# 2014_carte_alim.net
KiCad netlist of a schematic drawn in Altium Designer
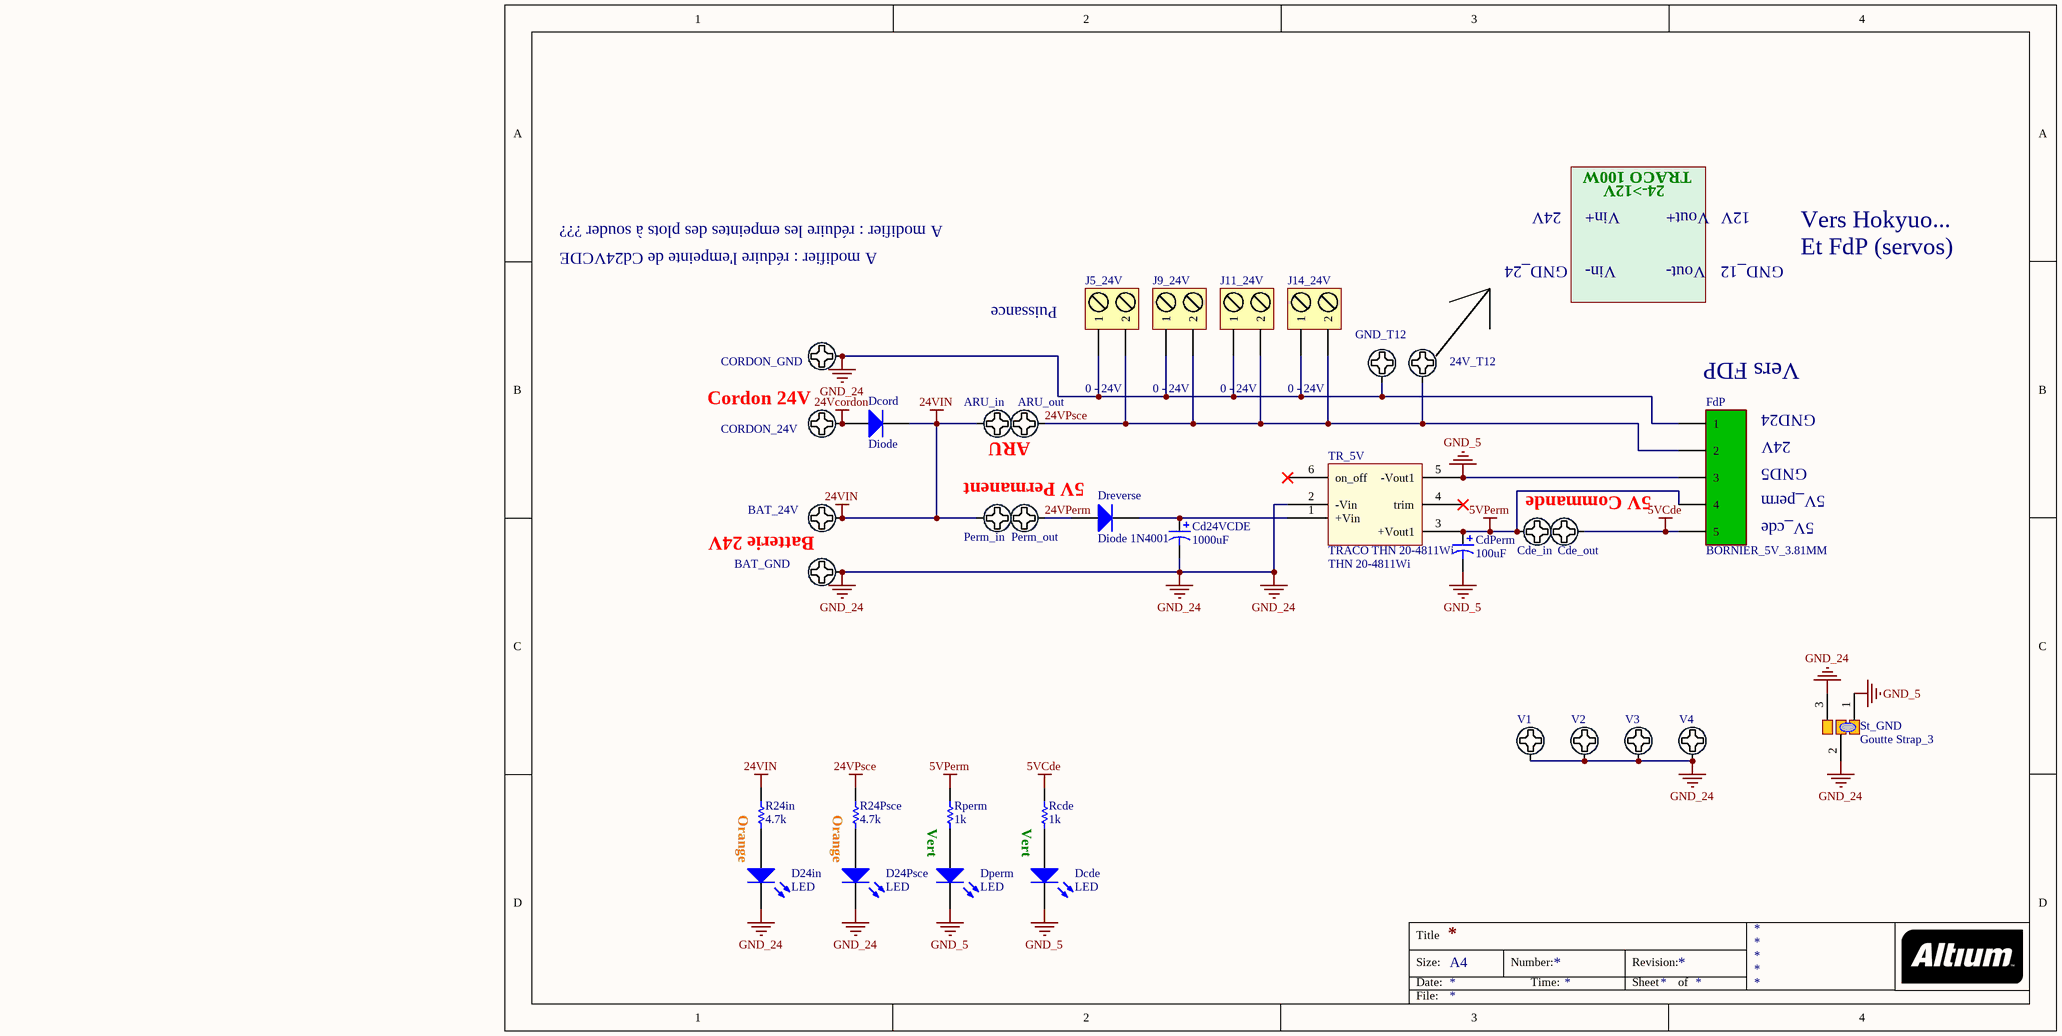
[diagram p0: 2014_carte_alim.SchDoc]

(export (version "E")
  (design (tool "Eeschema 10.0.6"))
  (components
    (comp (ref "24V_T12")
      (value "Pad_M3")
      (footprint "M3x6mm")
      (description "Vis M3 X 6mm _TORX_Tête 6mm")
      (fields (field (name "PUBLISHER") "Damien Guitton"))
      (libsource (lib "_ROBOT") (part "Vis M3 X 6mm _TORX_Tête 6mm"))
    )
    (comp (ref "ARU_in")
      (value "Pad_M3")
      (footprint "M3x6mm")
      (description "Vis M3 X 6mm _TORX_Tête 6mm")
      (fields (field (name "PUBLISHER") "Damien Guitton"))
      (libsource (lib "_ROBOT") (part "Vis M3 X 6mm _TORX_Tête 6mm"))
    )
    (comp (ref "ARU_out")
      (value "Pad_M3")
      (footprint "M3x6mm")
      (description "Vis M3 X 6mm _TORX_Tête 6mm")
      (fields (field (name "PUBLISHER") "Damien Guitton"))
      (libsource (lib "_ROBOT") (part "Vis M3 X 6mm _TORX_Tête 6mm"))
    )
    (comp (ref "BAT_24V")
      (value "Pad_M3")
      (footprint "M3x6mm")
      (description "Vis M3 X 6mm _TORX_Tête 6mm")
      (fields (field (name "PUBLISHER") "Damien Guitton"))
      (libsource (lib "_ROBOT") (part "Vis M3 X 6mm _TORX_Tête 6mm"))
    )
    (comp (ref "BAT_GND")
      (value "Pad_M3")
      (footprint "M3x6mm")
      (description "Vis M3 X 6mm _TORX_Tête 6mm")
      (fields (field (name "PUBLISHER") "Damien Guitton"))
      (libsource (lib "_ROBOT") (part "Vis M3 X 6mm _TORX_Tête 6mm"))
    )
    (comp (ref "Cd24VCDE")
      (value "1000uF")
      (footprint "RESISTANCE_5W")
      (description "Polarized Capacitor")
      (libsource (lib "_ROBOT") (part "Condensateur Polarise Traversant"))
    )
    (comp (ref "Cde_in")
      (value "Pad_M3")
      (footprint "M3x6mm")
      (description "Vis M3 X 6mm _TORX_Tête 6mm")
      (fields (field (name "PUBLISHER") "Damien Guitton"))
      (libsource (lib "_ROBOT") (part "Vis M3 X 6mm _TORX_Tête 6mm"))
    )
    (comp (ref "Cde_out")
      (value "Pad_M3")
      (footprint "M3x6mm")
      (description "Vis M3 X 6mm _TORX_Tête 6mm")
      (fields (field (name "PUBLISHER") "Damien Guitton"))
      (libsource (lib "_ROBOT") (part "Vis M3 X 6mm _TORX_Tête 6mm"))
    )
    (comp (ref "CdPerm")
      (value "100uF")
      (footprint "CAPPR5-10X12.5_3D")
      (description "Polarized Capacitor")
      (libsource (lib "_ROBOT") (part "Condensateur Polarise Traversant"))
    )
    (comp (ref "CORDON_24V")
      (value "Pad_M3")
      (footprint "M3x6mm")
      (description "Vis M3 X 6mm _TORX_Tête 6mm")
      (fields (field (name "PUBLISHER") "Damien Guitton"))
      (libsource (lib "_ROBOT") (part "Vis M3 X 6mm _TORX_Tête 6mm"))
    )
    (comp (ref "CORDON_GND")
      (value "Pad_M3")
      (footprint "M3x6mm")
      (description "Vis M3 X 6mm _TORX_Tête 6mm")
      (fields (field (name "PUBLISHER") "Damien Guitton"))
      (libsource (lib "_ROBOT") (part "Vis M3 X 6mm _TORX_Tête 6mm"))
    )
    (comp (ref "D24in")
      (value "LED")
      (footprint "LED_0805")
      (description "Typical LED")
      (fields (field (name "PUBLISHER") "Altium Limited"))
      (libsource (lib "_ROBOT") (part "LED"))
    )
    (comp (ref "D24Psce")
      (value "LED")
      (footprint "LED_0805")
      (description "Typical LED")
      (fields (field (name "PUBLISHER") "Altium Limited"))
      (libsource (lib "_ROBOT") (part "LED"))
    )
    (comp (ref "Dcde")
      (value "LED")
      (footprint "LED_0805")
      (description "Typical LED")
      (fields (field (name "PUBLISHER") "Altium Limited"))
      (libsource (lib "_ROBOT") (part "LED"))
    )
    (comp (ref "Dcord")
      (value "Diode")
      (footprint "DIO10.46-5.3x2.8")
      (description "1 Amp General Purpose Rectifier")
      (fields (field (name "PUBLISHER") "Altium Limited"))
      (libsource (lib "Miscellaneous Devices") (part "Diode 1N4001"))
    )
    (comp (ref "Dperm")
      (value "LED")
      (footprint "LED_0805")
      (description "Typical LED")
      (fields (field (name "PUBLISHER") "Altium Limited"))
      (libsource (lib "_ROBOT") (part "LED"))
    )
    (comp (ref "Dreverse")
      (value "Diode 1N4001")
      (footprint "DIO10.46-5.3x2.8")
      (description "1 Amp General Purpose Rectifier")
      (fields (field (name "PUBLISHER") "Altium Limited"))
      (libsource (lib "Miscellaneous Devices") (part "Diode 1N4001"))
    )
    (comp (ref "FdP")
      (value "BORNIER_5V_3.81MM")
      (footprint "BORNIER_5V_3.81MM")
      (libsource (lib "Connecteur") (part "BORNIER_5V_3.81MM"))
    )
    (comp (ref "GND_T12")
      (value "Pad_M3")
      (footprint "M3x6mm")
      (description "Vis M3 X 6mm _TORX_Tête 6mm")
      (fields (field (name "PUBLISHER") "Damien Guitton"))
      (libsource (lib "_ROBOT") (part "Vis M3 X 6mm _TORX_Tête 6mm"))
    )
    (comp (ref "J5_24V")
      (value "0 - 24V")
      (footprint "BORNIER2_FEM_COUDE")
      (description "Terminal blocks, 2 pins, pitch=5mm")
      (libsource (lib "miniprojet") (part "BORNIER2"))
    )
    (comp (ref "J9_24V")
      (value "0 - 24V")
      (footprint "BORNIER2_FEM_COUDE")
      (description "Terminal blocks, 2 pins, pitch=5mm")
      (libsource (lib "miniprojet") (part "BORNIER2"))
    )
    (comp (ref "J11_24V")
      (value "0 - 24V")
      (footprint "BORNIER2_FEM_COUDE")
      (description "Terminal blocks, 2 pins, pitch=5mm")
      (libsource (lib "miniprojet") (part "BORNIER2"))
    )
    (comp (ref "J14_24V")
      (value "0 - 24V")
      (footprint "BORNIER2_FEM_COUDE")
      (description "Terminal blocks, 2 pins, pitch=5mm")
      (libsource (lib "miniprojet") (part "BORNIER2"))
    )
    (comp (ref "Perm_in")
      (value "Pad_M3")
      (footprint "M3x6mm")
      (description "Vis M3 X 6mm _TORX_Tête 6mm")
      (fields (field (name "PUBLISHER") "Damien Guitton"))
      (libsource (lib "_ROBOT") (part "Vis M3 X 6mm _TORX_Tête 6mm"))
    )
    (comp (ref "Perm_out")
      (value "Pad_M3")
      (footprint "M3x6mm")
      (description "Vis M3 X 6mm _TORX_Tête 6mm")
      (fields (field (name "PUBLISHER") "Damien Guitton"))
      (libsource (lib "_ROBOT") (part "Vis M3 X 6mm _TORX_Tête 6mm"))
    )
    (comp (ref "R24in")
      (value "4.7k")
      (footprint "R1206_N")
      (description "Resistor")
      (fields (field (name "PUBLISHER") "Altium Limited"))
      (libsource (lib "_ROBOT") (part "Resistor"))
    )
    (comp (ref "R24Psce")
      (value "4.7k")
      (footprint "R1206_N")
      (description "Resistor")
      (fields (field (name "PUBLISHER") "Altium Limited"))
      (libsource (lib "_ROBOT") (part "Resistor"))
    )
    (comp (ref "Rcde")
      (value "1k")
      (footprint "R1206_N")
      (description "Resistor")
      (fields (field (name "PUBLISHER") "Altium Limited"))
      (libsource (lib "_ROBOT") (part "Resistor"))
    )
    (comp (ref "Rperm")
      (value "1k")
      (footprint "R1206_N")
      (description "Resistor")
      (fields (field (name "PUBLISHER") "Altium Limited"))
      (libsource (lib "_ROBOT") (part "Resistor"))
    )
    (comp (ref "St_GND")
      (value "Goutte Strap_3")
      (footprint "Goutte Strap_3")
      (fields (field (name "PUBLISHER") "Damien Guitton"))
      (libsource (lib "DG_Connecteur") (part "Goutte Strap_3"))
    )
    (comp (ref "TR_5V")
      (value "TRACO THN 20-4811Wi")
      (footprint "TRACO_THN20")
      (description "Traco 20W 24V to 5V*4A")
      (fields (field (name "REF") "THN 20-4811Wi"))
      (libsource (lib "_ROBOT") (part "TRACO THN 20-4811Wi"))
    )
    (comp (ref "V1")
      (value "Pad_M3")
      (footprint "M3x6mm")
      (description "Vis M3 X 6mm _TORX_Tête 6mm")
      (fields (field (name "PUBLISHER") "Damien Guitton"))
      (libsource (lib "_ROBOT") (part "Vis M3 X 6mm _TORX_Tête 6mm"))
    )
    (comp (ref "V2")
      (value "Pad_M3")
      (footprint "M3x6mm")
      (description "Vis M3 X 6mm _TORX_Tête 6mm")
      (fields (field (name "PUBLISHER") "Damien Guitton"))
      (libsource (lib "_ROBOT") (part "Vis M3 X 6mm _TORX_Tête 6mm"))
    )
    (comp (ref "V3")
      (value "Pad_M3")
      (footprint "M3x6mm")
      (description "Vis M3 X 6mm _TORX_Tête 6mm")
      (fields (field (name "PUBLISHER") "Damien Guitton"))
      (libsource (lib "_ROBOT") (part "Vis M3 X 6mm _TORX_Tête 6mm"))
    )
    (comp (ref "V4")
      (value "Pad_M3")
      (footprint "M3x6mm")
      (description "Vis M3 X 6mm _TORX_Tête 6mm")
      (fields (field (name "PUBLISHER") "Damien Guitton"))
      (libsource (lib "_ROBOT") (part "Vis M3 X 6mm _TORX_Tête 6mm"))
    )
  )
  (nets
    (net (code "1") (name "/24VPerm") (class "Default")
      (node (ref "Dreverse") (pin "1") (pinfunction "A_1") (pintype "passive"))
      (node (ref "Perm_out") (pin "1") (pinfunction "1_1") (pintype "passive"))
    )
    (net (code "2") (name "5VCde") (class "Default")
      (node (ref "Cde_out") (pin "1") (pinfunction "1_1") (pintype "passive"))
      (node (ref "FdP") (pin "5") (pinfunction "5_5") (pintype "passive"))
      (node (ref "Rcde") (pin "1") (pinfunction "1_1") (pintype "passive"))
    )
    (net (code "3") (name "5VPerm") (class "Default")
      (node (ref "CdPerm") (pin "1") (pinfunction "1_1") (pintype "passive"))
      (node (ref "Cde_in") (pin "1") (pinfunction "1_1") (pintype "passive"))
      (node (ref "FdP") (pin "4") (pinfunction "4_4") (pintype "passive"))
      (node (ref "Rperm") (pin "1") (pinfunction "1_1") (pintype "passive"))
      (node (ref "TR_5V") (pin "3") (pinfunction "+Vout1_3") (pintype "passive"))
    )
    (net (code "4") (name "24VIN") (class "Default")
      (node (ref "ARU_in") (pin "1") (pinfunction "1_1") (pintype "passive"))
      (node (ref "BAT_24V") (pin "1") (pinfunction "1_1") (pintype "passive"))
      (node (ref "Dcord") (pin "2") (pinfunction "K_2") (pintype "passive"))
      (node (ref "Perm_in") (pin "1") (pinfunction "1_1") (pintype "passive"))
      (node (ref "R24in") (pin "1") (pinfunction "1_1") (pintype "passive"))
    )
    (net (code "5") (name "24VPsce") (class "Default")
      (node (ref "24V_T12") (pin "1") (pinfunction "1_1") (pintype "passive"))
      (node (ref "ARU_out") (pin "1") (pinfunction "1_1") (pintype "passive"))
      (node (ref "FdP") (pin "2") (pinfunction "2_2") (pintype "passive"))
      (node (ref "J11_24V") (pin "2") (pinfunction "2_2") (pintype "passive"))
      (node (ref "J14_24V") (pin "2") (pinfunction "2_2") (pintype "passive"))
      (node (ref "J5_24V") (pin "2") (pinfunction "2_2") (pintype "passive"))
      (node (ref "J9_24V") (pin "2") (pinfunction "2_2") (pintype "passive"))
      (node (ref "R24Psce") (pin "1") (pinfunction "1_1") (pintype "passive"))
    )
    (net (code "6") (name "24Vcordon") (class "Default")
      (node (ref "CORDON_24V") (pin "1") (pinfunction "1_1") (pintype "passive"))
      (node (ref "Dcord") (pin "1") (pinfunction "A_1") (pintype "passive"))
    )
    (net (code "7") (name "GND_5") (class "Default")
      (node (ref "CdPerm") (pin "2") (pinfunction "2_2") (pintype "passive"))
      (node (ref "Dcde") (pin "2") (pinfunction "K_2") (pintype "passive"))
      (node (ref "Dperm") (pin "2") (pinfunction "K_2") (pintype "passive"))
      (node (ref "FdP") (pin "3") (pinfunction "3_3") (pintype "passive"))
      (node (ref "St_GND") (pin "1") (pinfunction "1_1") (pintype "passive"))
      (node (ref "TR_5V") (pin "5") (pinfunction "-Vout1_5") (pintype "passive"))
    )
    (net (code "8") (name "GND_24") (class "Default")
      (node (ref "BAT_GND") (pin "1") (pinfunction "1_1") (pintype "passive"))
      (node (ref "CORDON_GND") (pin "1") (pinfunction "1_1") (pintype "passive"))
      (node (ref "Cd24VCDE") (pin "2") (pinfunction "2_2") (pintype "passive"))
      (node (ref "D24Psce") (pin "2") (pinfunction "K_2") (pintype "passive"))
      (node (ref "D24in") (pin "2") (pinfunction "K_2") (pintype "passive"))
      (node (ref "FdP") (pin "1") (pinfunction "1_1") (pintype "passive"))
      (node (ref "GND_T12") (pin "1") (pinfunction "1_1") (pintype "passive"))
      (node (ref "J11_24V") (pin "1") (pinfunction "1_1") (pintype "passive"))
      (node (ref "J14_24V") (pin "1") (pinfunction "1_1") (pintype "passive"))
      (node (ref "J5_24V") (pin "1") (pinfunction "1_1") (pintype "passive"))
      (node (ref "J9_24V") (pin "1") (pinfunction "1_1") (pintype "passive"))
      (node (ref "St_GND") (pin "2") (pinfunction "2_2") (pintype "passive"))
      (node (ref "St_GND") (pin "3") (pinfunction "3_3") (pintype "passive"))
      (node (ref "TR_5V") (pin "2") (pinfunction "-Vin_2") (pintype "passive"))
      (node (ref "V1") (pin "1") (pinfunction "1_1") (pintype "passive"))
      (node (ref "V2") (pin "1") (pinfunction "1_1") (pintype "passive"))
      (node (ref "V3") (pin "1") (pinfunction "1_1") (pintype "passive"))
      (node (ref "V4") (pin "1") (pinfunction "1_1") (pintype "passive"))
    )
    (net (code "9") (name "Net-(D24Psce-A)") (class "Default")
      (node (ref "D24Psce") (pin "1") (pinfunction "A_1") (pintype "passive"))
      (node (ref "R24Psce") (pin "2") (pinfunction "2_2") (pintype "passive"))
    )
    (net (code "10") (name "Net-(D24in-A)") (class "Default")
      (node (ref "D24in") (pin "1") (pinfunction "A_1") (pintype "passive"))
      (node (ref "R24in") (pin "2") (pinfunction "2_2") (pintype "passive"))
    )
    (net (code "11") (name "Net-(Dcde-A)") (class "Default")
      (node (ref "Dcde") (pin "1") (pinfunction "A_1") (pintype "passive"))
      (node (ref "Rcde") (pin "2") (pinfunction "2_2") (pintype "passive"))
    )
    (net (code "12") (name "Net-(Dperm-A)") (class "Default")
      (node (ref "Dperm") (pin "1") (pinfunction "A_1") (pintype "passive"))
      (node (ref "Rperm") (pin "2") (pinfunction "2_2") (pintype "passive"))
    )
    (net (code "13") (name "Net-(Dreverse-K)") (class "Default")
      (node (ref "Cd24VCDE") (pin "1") (pinfunction "1_1") (pintype "passive"))
      (node (ref "Dreverse") (pin "2") (pinfunction "K_2") (pintype "passive"))
      (node (ref "TR_5V") (pin "1") (pinfunction "+Vin_1") (pintype "passive"))
    )
    (net (code "14") (name "unconnected-(TR_5V-on_off-Pad6)") (class "Default")
      (node (ref "TR_5V") (pin "6") (pinfunction "on_off_6") (pintype "passive+no_connect"))
    )
    (net (code "15") (name "unconnected-(TR_5V-trim-Pad4)") (class "Default")
      (node (ref "TR_5V") (pin "4") (pinfunction "trim_4") (pintype "passive+no_connect"))
    )
  )
)
